# QMI8658C.net
KiCad netlist of a schematic drawn in Altium Designer
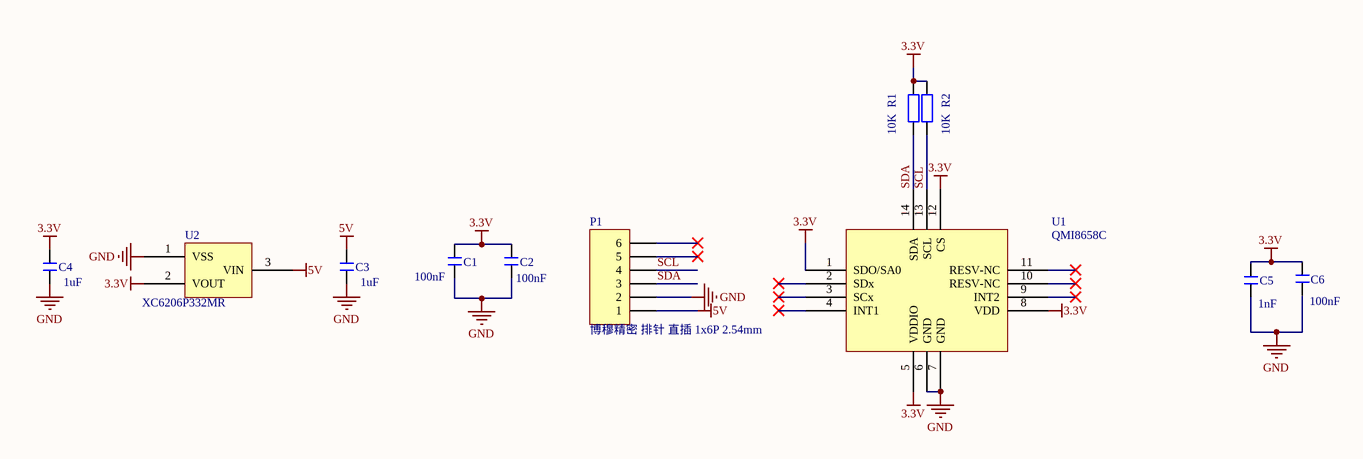
[diagram p0: QMI8658C.SchDoc]

(export (version "E")
  (design (tool "Eeschema 10.0.6"))
  (components
    (comp (ref "C1")
      (value "100nF 10% X7R 50V 0603")
      (footprint "C 0603_M")
      (description "无极性贴片电容")
      (fields (field (name "值") "100nF"))
      (libsource (lib "3.1   - 电阻-电容-电感") (part "C"))
    )
    (comp (ref "C2")
      (value "100nF 10% X7R 50V 0603")
      (footprint "C 0603_M")
      (description "无极性贴片电容")
      (fields (field (name "值") "100nF"))
      (libsource (lib "3.1   - 电阻-电容-电感") (part "C"))
    )
    (comp (ref "C3")
      (value "1uF 10% X7R 50V 0603")
      (footprint "C 0603_M")
      (description "无极性贴片电容")
      (fields (field (name "值") "1uF"))
      (libsource (lib "3.1   - 电阻-电容-电感") (part "C"))
    )
    (comp (ref "C4")
      (value "1uF 10% X7R 50V 0603")
      (footprint "C 0603_M")
      (description "无极性贴片电容")
      (fields (field (name "值") "1uF"))
      (libsource (lib "3.1   - 电阻-电容-电感") (part "C"))
    )
    (comp (ref "C5")
      (value "1nF 10% X7R 50V 0603")
      (footprint "C 0603_M")
      (description "无极性贴片电容")
      (fields (field (name "值") "1nF"))
      (libsource (lib "3.1   - 电阻-电容-电感") (part "C"))
    )
    (comp (ref "C6")
      (value "100nF 10% X7R 50V 0603")
      (footprint "C 0603_M")
      (description "无极性贴片电容")
      (fields (field (name "值") "100nF"))
      (libsource (lib "3.1   - 电阻-电容-电感") (part "C"))
    )
    (comp (ref "P1")
      (value "博穆精密 排针 直插 1x6P 2.54mm")
      (footprint "HDR1X6")
      (description "Header, 6-Pin")
      (libsource (lib "Miscellaneous Connectors") (part "Header 6"))
    )
    (comp (ref "R1")
      (value "10K 5% 1/10W 0603")
      (footprint "R 0603_M")
      (description "贴片电阻")
      (fields (field (name "值") "10K"))
      (libsource (lib "3.1   - 电阻-电容-电感") (part "R"))
    )
    (comp (ref "R2")
      (value "10K 5% 1/10W 0603")
      (footprint "R 0603_M")
      (description "贴片电阻")
      (fields (field (name "值") "10K"))
      (libsource (lib "3.1   - 电阻-电容-电感") (part "R"))
    )
    (comp (ref "U1")
      (value "QMI8658C")
      (footprint "LGA-14_L3.0-W2.5-P0.50-BR - duplicate")
      (libsource (lib "Schlib1") (part "QMI8658C"))
    )
    (comp (ref "U2")
      (value "线性电源IC  UMW XC6206P332MR,SOT23")
      (footprint "SOT-23-3_L3.0-W1.7-P0.95-LS2.9-BR")
      (fields (field (name "值") "XC6206P332MR"))
      (libsource (lib "Schlib1") (part "XC6206P332MR"))
    )
  )
  (nets
    (net (code "1") (name "/SCL") (class "Default")
      (node (ref "P1") (pin "4") (pinfunction "4_4") (pintype "passive"))
      (node (ref "R2") (pin "1") (pinfunction "1_1") (pintype "passive"))
      (node (ref "U1") (pin "13") (pinfunction "SCL_13") (pintype "passive"))
    )
    (net (code "2") (name "/SDA") (class "Default")
      (node (ref "P1") (pin "3") (pinfunction "3_3") (pintype "passive"))
      (node (ref "R1") (pin "1") (pinfunction "1_1") (pintype "passive"))
      (node (ref "U1") (pin "14") (pinfunction "SDA_14") (pintype "passive"))
    )
    (net (code "3") (name "3.3V") (class "Default")
      (node (ref "C1") (pin "2") (pinfunction "2_2") (pintype "passive"))
      (node (ref "C2") (pin "2") (pinfunction "2_2") (pintype "passive"))
      (node (ref "C4") (pin "2") (pinfunction "2_2") (pintype "passive"))
      (node (ref "C5") (pin "2") (pinfunction "2_2") (pintype "passive"))
      (node (ref "C6") (pin "2") (pinfunction "2_2") (pintype "passive"))
      (node (ref "R1") (pin "2") (pinfunction "2_2") (pintype "passive"))
      (node (ref "R2") (pin "2") (pinfunction "2_2") (pintype "passive"))
      (node (ref "U1") (pin "1") (pinfunction "SDO/SA0_1") (pintype "passive"))
      (node (ref "U1") (pin "12") (pinfunction "CS_12") (pintype "passive"))
      (node (ref "U1") (pin "5") (pinfunction "VDDIO_5") (pintype "passive"))
      (node (ref "U1") (pin "8") (pinfunction "VDD_8") (pintype "passive"))
      (node (ref "U2") (pin "2") (pinfunction "VOUT_2") (pintype "passive"))
    )
    (net (code "4") (name "5V") (class "Default")
      (node (ref "C3") (pin "2") (pinfunction "2_2") (pintype "passive"))
      (node (ref "P1") (pin "1") (pinfunction "1_1") (pintype "passive"))
      (node (ref "U2") (pin "3") (pinfunction "VIN_3") (pintype "passive"))
    )
    (net (code "5") (name "GND") (class "Default")
      (node (ref "C1") (pin "1") (pinfunction "1_1") (pintype "passive"))
      (node (ref "C2") (pin "1") (pinfunction "1_1") (pintype "passive"))
      (node (ref "C3") (pin "1") (pinfunction "1_1") (pintype "passive"))
      (node (ref "C4") (pin "1") (pinfunction "1_1") (pintype "passive"))
      (node (ref "C5") (pin "1") (pinfunction "1_1") (pintype "passive"))
      (node (ref "C6") (pin "1") (pinfunction "1_1") (pintype "passive"))
      (node (ref "P1") (pin "2") (pinfunction "2_2") (pintype "passive"))
      (node (ref "U1") (pin "6") (pinfunction "GND_6") (pintype "passive"))
      (node (ref "U1") (pin "7") (pinfunction "GND_7") (pintype "passive"))
      (node (ref "U2") (pin "1") (pinfunction "VSS_1") (pintype "passive"))
    )
    (net (code "6") (name "unconnected-(P1-Pad5)") (class "Default")
      (node (ref "P1") (pin "5") (pinfunction "5_5") (pintype "passive+no_connect"))
    )
    (net (code "7") (name "unconnected-(P1-Pad6)") (class "Default")
      (node (ref "P1") (pin "6") (pinfunction "6_6") (pintype "passive+no_connect"))
    )
    (net (code "8") (name "unconnected-(U1-INT1-Pad4)") (class "Default")
      (node (ref "U1") (pin "4") (pinfunction "INT1_4") (pintype "passive+no_connect"))
    )
    (net (code "9") (name "unconnected-(U1-INT2-Pad9)") (class "Default")
      (node (ref "U1") (pin "9") (pinfunction "INT2_9") (pintype "passive+no_connect"))
    )
    (net (code "10") (name "unconnected-(U1-RESV-NC-Pad10)") (class "Default")
      (node (ref "U1") (pin "10") (pinfunction "RESV-NC_10") (pintype "passive+no_connect"))
    )
    (net (code "11") (name "unconnected-(U1-RESV-NC-Pad11)") (class "Default")
      (node (ref "U1") (pin "11") (pinfunction "RESV-NC_11") (pintype "passive+no_connect"))
    )
    (net (code "12") (name "unconnected-(U1-SCx-Pad3)") (class "Default")
      (node (ref "U1") (pin "3") (pinfunction "SCx_3") (pintype "passive+no_connect"))
    )
    (net (code "13") (name "unconnected-(U1-SDx-Pad2)") (class "Default")
      (node (ref "U1") (pin "2") (pinfunction "SDx_2") (pintype "passive+no_connect"))
    )
  )
)
